# ELECTRON-.net
KiCad netlist of a schematic drawn in EAGLE
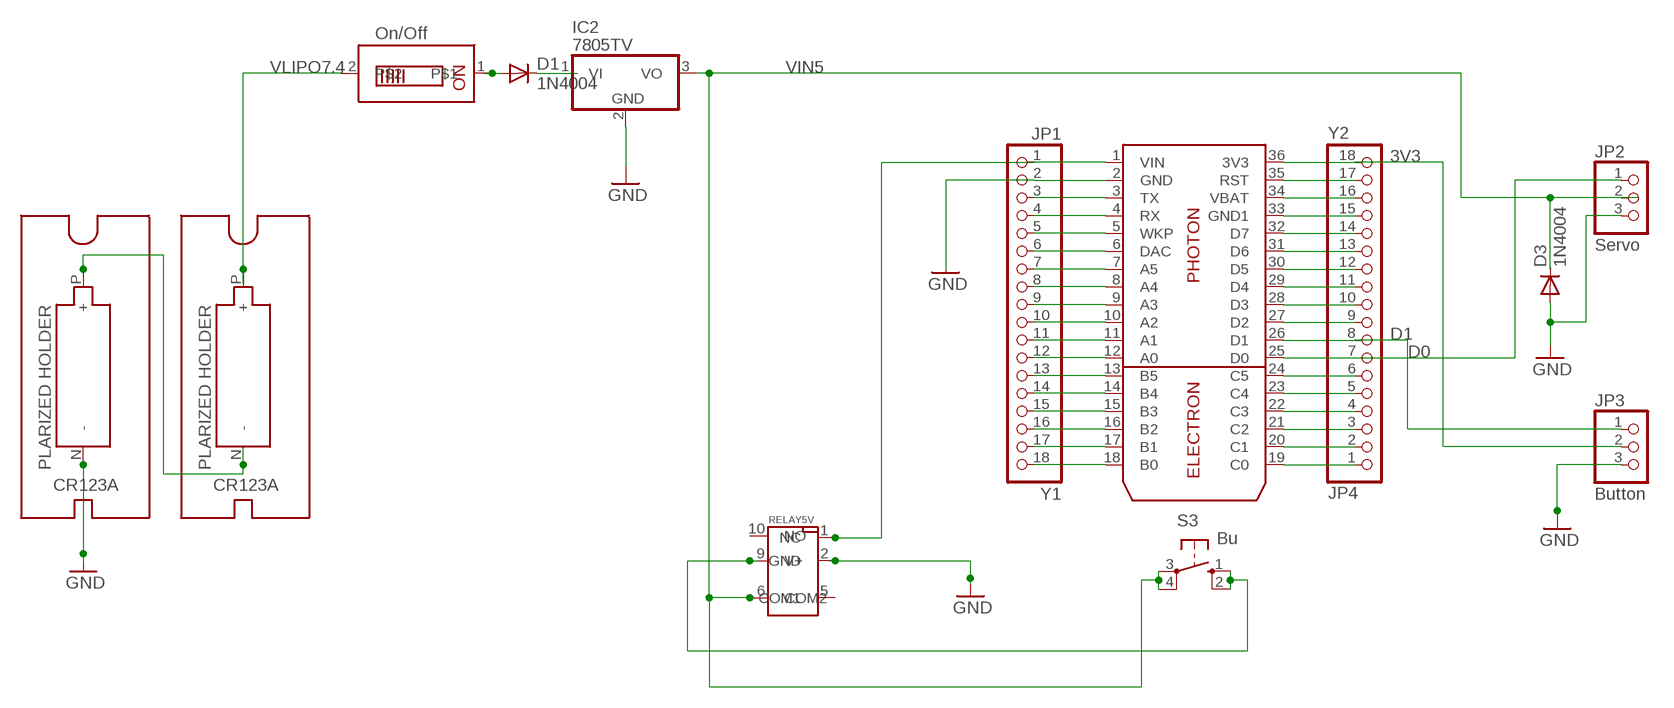
[diagram p0: schematic, sheet 1]

(export (version "E")
  (design (tool "Eeschema 10.0.6"))
  (components
    (comp (ref "D1")
      (value "1N4004")
      (footprint "eagle-import:DO41-10")
      (libsource (lib "eagle-import") (part "1N4004"))
    )
    (comp (ref "D3")
      (value "1N4004")
      (footprint "eagle-import:DO41-10")
      (libsource (lib "eagle-import") (part "1N4004"))
    )
    (comp (ref "ELECTRON2")
      (value "ELECTRON")
      (footprint "eagle-import:ELECTRON-U260")
      (libsource (lib "eagle-import") (part "ELECTRON"))
    )
    (comp (ref "IC2")
      (value "7805TV")
      (footprint "eagle-import:TO220V")
      (libsource (lib "eagle-import") (part "78TV05"))
    )
    (comp (ref "JP1")
      (value "Y1")
      (footprint "eagle-import:1X18")
      (libsource (lib "eagle-import") (part "PINHD-1X18"))
    )
    (comp (ref "JP2")
      (value "Servo")
      (footprint "eagle-import:1X03_90")
      (libsource (lib "eagle-import") (part "PINHD-1X3/90"))
    )
    (comp (ref "JP3")
      (value "Button")
      (footprint "eagle-import:1X03_90")
      (libsource (lib "eagle-import") (part "PINHD-1X3/90"))
    )
    (comp (ref "JP4")
      (value "Y2")
      (footprint "eagle-import:1X18")
      (libsource (lib "eagle-import") (part "PINHD-1X18"))
    )
    (comp (ref "S3")
      (value "Bu")
      (footprint "eagle-import:B3F-10XX")
      (fields (field (name "MPN") "B3F-1000"))
      (libsource (lib "eagle-import") (part "10-XX"))
    )
    (comp (ref "U$1")
      (value "POLARIZEDHOLDER-CR123A")
      (footprint "eagle-import:CRT123A")
      (libsource (lib "eagle-import") (part "POLARIZEDHOLDER-CR123A"))
    )
    (comp (ref "U$2")
      (value "POLARIZEDHOLDER-CR123A")
      (footprint "eagle-import:CRT123A")
      (libsource (lib "eagle-import") (part "POLARIZEDHOLDER-CR123A"))
    )
    (comp (ref "U$3")
      (value "SWIDGET")
      (footprint "eagle-import:GF-123-0054")
      (libsource (lib "eagle-import") (part "SWIDGET"))
    )
    (comp (ref "U$4")
      (value "RELAY5V")
      (footprint "eagle-import:RELAY5V-F")
      (libsource (lib "eagle-import") (part "RELAY5V"))
    )
  )
  (nets
    (net (code "1") (name "/3V3") (class "Default")
      (node (ref "ELECTRON2") (pin "36") (pinfunction "3V3_36") (pintype "bidirectional"))
      (node (ref "JP3") (pin "2") (pinfunction "2_2") (pintype "passive"))
      (node (ref "JP4") (pin "18") (pinfunction "18_18") (pintype "passive"))
    )
    (net (code "2") (name "/D0") (class "Default")
      (node (ref "ELECTRON2") (pin "25") (pinfunction "D0_25") (pintype "bidirectional"))
      (node (ref "JP2") (pin "1") (pinfunction "1_1") (pintype "passive"))
      (node (ref "JP4") (pin "7") (pinfunction "7_7") (pintype "passive"))
    )
    (net (code "3") (name "/D1") (class "Default")
      (node (ref "ELECTRON2") (pin "26") (pinfunction "D1_26") (pintype "bidirectional"))
      (node (ref "JP3") (pin "1") (pinfunction "1_1") (pintype "passive"))
      (node (ref "JP4") (pin "8") (pinfunction "8_8") (pintype "passive"))
    )
    (net (code "4") (name "/VIN5") (class "Default")
      (node (ref "D3") (pin "C") (pinfunction "C_C") (pintype "passive"))
      (node (ref "IC2") (pin "3") (pinfunction "VO_3") (pintype "passive"))
      (node (ref "JP2") (pin "2") (pinfunction "2_2") (pintype "passive"))
      (node (ref "S3") (pin "3") (pinfunction "P_3") (pintype "passive"))
      (node (ref "S3") (pin "4") (pinfunction "P1_4") (pintype "passive"))
      (node (ref "U$4") (pin "6") (pinfunction "COM2_6") (pintype "bidirectional"))
    )
    (net (code "5") (name "/VLIPO7.4") (class "Default")
      (node (ref "U$2") (pin "P") (pinfunction "+_P") (pintype "bidirectional"))
      (node (ref "U$3") (pin "2") (pinfunction "P$2_2") (pintype "bidirectional"))
    )
    (net (code "6") (name "GND") (class "Default")
      (node (ref "D3") (pin "A") (pinfunction "A_A") (pintype "passive"))
      (node (ref "ELECTRON2") (pin "2") (pinfunction "GND_2") (pintype "bidirectional"))
      (node (ref "IC2") (pin "2") (pinfunction "GND_2") (pintype "passive"))
      (node (ref "JP1") (pin "2") (pinfunction "2_2") (pintype "passive"))
      (node (ref "JP2") (pin "3") (pinfunction "3_3") (pintype "passive"))
      (node (ref "JP3") (pin "3") (pinfunction "3_3") (pintype "passive"))
      (node (ref "U$1") (pin "N") (pinfunction "-_N") (pintype "bidirectional"))
      (node (ref "U$4") (pin "2") (pinfunction "GND_2") (pintype "bidirectional"))
    )
    (net (code "7") (name "Net-(ELECTRON2-A0)") (class "Default")
      (node (ref "ELECTRON2") (pin "12") (pinfunction "A0_12") (pintype "bidirectional"))
      (node (ref "JP1") (pin "12") (pinfunction "12_12") (pintype "passive"))
    )
    (net (code "8") (name "Net-(ELECTRON2-A1)") (class "Default")
      (node (ref "ELECTRON2") (pin "11") (pinfunction "A1_11") (pintype "bidirectional"))
      (node (ref "JP1") (pin "11") (pinfunction "11_11") (pintype "passive"))
    )
    (net (code "9") (name "Net-(ELECTRON2-A2)") (class "Default")
      (node (ref "ELECTRON2") (pin "10") (pinfunction "A2_10") (pintype "bidirectional"))
      (node (ref "JP1") (pin "10") (pinfunction "10_10") (pintype "passive"))
    )
    (net (code "10") (name "Net-(ELECTRON2-A3)") (class "Default")
      (node (ref "ELECTRON2") (pin "9") (pinfunction "A3_9") (pintype "bidirectional"))
      (node (ref "JP1") (pin "9") (pinfunction "9_9") (pintype "passive"))
    )
    (net (code "11") (name "Net-(ELECTRON2-A4)") (class "Default")
      (node (ref "ELECTRON2") (pin "8") (pinfunction "A4_8") (pintype "bidirectional"))
      (node (ref "JP1") (pin "8") (pinfunction "8_8") (pintype "passive"))
    )
    (net (code "12") (name "Net-(ELECTRON2-A5)") (class "Default")
      (node (ref "ELECTRON2") (pin "7") (pinfunction "A5_7") (pintype "bidirectional"))
      (node (ref "JP1") (pin "7") (pinfunction "7_7") (pintype "passive"))
    )
    (net (code "13") (name "Net-(ELECTRON2-B0)") (class "Default")
      (node (ref "ELECTRON2") (pin "18") (pinfunction "B0_18") (pintype "bidirectional"))
      (node (ref "JP1") (pin "18") (pinfunction "18_18") (pintype "passive"))
    )
    (net (code "14") (name "Net-(ELECTRON2-B1)") (class "Default")
      (node (ref "ELECTRON2") (pin "17") (pinfunction "B1_17") (pintype "bidirectional"))
      (node (ref "JP1") (pin "17") (pinfunction "17_17") (pintype "passive"))
    )
    (net (code "15") (name "Net-(ELECTRON2-B2)") (class "Default")
      (node (ref "ELECTRON2") (pin "16") (pinfunction "B2_16") (pintype "bidirectional"))
      (node (ref "JP1") (pin "16") (pinfunction "16_16") (pintype "passive"))
    )
    (net (code "16") (name "Net-(ELECTRON2-B3)") (class "Default")
      (node (ref "ELECTRON2") (pin "15") (pinfunction "B3_15") (pintype "bidirectional"))
      (node (ref "JP1") (pin "15") (pinfunction "15_15") (pintype "passive"))
    )
    (net (code "17") (name "Net-(ELECTRON2-B4)") (class "Default")
      (node (ref "ELECTRON2") (pin "14") (pinfunction "B4_14") (pintype "bidirectional"))
      (node (ref "JP1") (pin "14") (pinfunction "14_14") (pintype "passive"))
    )
    (net (code "18") (name "Net-(ELECTRON2-B5)") (class "Default")
      (node (ref "ELECTRON2") (pin "13") (pinfunction "B5_13") (pintype "bidirectional"))
      (node (ref "JP1") (pin "13") (pinfunction "13_13") (pintype "passive"))
    )
    (net (code "19") (name "Net-(ELECTRON2-C0)") (class "Default")
      (node (ref "ELECTRON2") (pin "19") (pinfunction "C0_19") (pintype "bidirectional"))
      (node (ref "JP4") (pin "1") (pinfunction "1_1") (pintype "passive"))
    )
    (net (code "20") (name "Net-(ELECTRON2-C1)") (class "Default")
      (node (ref "ELECTRON2") (pin "20") (pinfunction "C1_20") (pintype "bidirectional"))
      (node (ref "JP4") (pin "2") (pinfunction "2_2") (pintype "passive"))
    )
    (net (code "21") (name "Net-(ELECTRON2-C2)") (class "Default")
      (node (ref "ELECTRON2") (pin "21") (pinfunction "C2_21") (pintype "bidirectional"))
      (node (ref "JP4") (pin "3") (pinfunction "3_3") (pintype "passive"))
    )
    (net (code "22") (name "Net-(ELECTRON2-C3)") (class "Default")
      (node (ref "ELECTRON2") (pin "22") (pinfunction "C3_22") (pintype "bidirectional"))
      (node (ref "JP4") (pin "4") (pinfunction "4_4") (pintype "passive"))
    )
    (net (code "23") (name "Net-(ELECTRON2-C4)") (class "Default")
      (node (ref "ELECTRON2") (pin "23") (pinfunction "C4_23") (pintype "bidirectional"))
      (node (ref "JP4") (pin "5") (pinfunction "5_5") (pintype "passive"))
    )
    (net (code "24") (name "Net-(ELECTRON2-C5)") (class "Default")
      (node (ref "ELECTRON2") (pin "24") (pinfunction "C5_24") (pintype "bidirectional"))
      (node (ref "JP4") (pin "6") (pinfunction "6_6") (pintype "passive"))
    )
    (net (code "25") (name "Net-(ELECTRON2-D2)") (class "Default")
      (node (ref "ELECTRON2") (pin "27") (pinfunction "D2_27") (pintype "bidirectional"))
      (node (ref "JP4") (pin "9") (pinfunction "9_9") (pintype "passive"))
    )
    (net (code "26") (name "Net-(ELECTRON2-D3)") (class "Default")
      (node (ref "ELECTRON2") (pin "28") (pinfunction "D3_28") (pintype "bidirectional"))
      (node (ref "JP4") (pin "10") (pinfunction "10_10") (pintype "passive"))
    )
    (net (code "27") (name "Net-(ELECTRON2-D4)") (class "Default")
      (node (ref "ELECTRON2") (pin "29") (pinfunction "D4_29") (pintype "bidirectional"))
      (node (ref "JP4") (pin "11") (pinfunction "11_11") (pintype "passive"))
    )
    (net (code "28") (name "Net-(ELECTRON2-D5)") (class "Default")
      (node (ref "ELECTRON2") (pin "30") (pinfunction "D5_30") (pintype "bidirectional"))
      (node (ref "JP4") (pin "12") (pinfunction "12_12") (pintype "passive"))
    )
    (net (code "29") (name "Net-(ELECTRON2-D6)") (class "Default")
      (node (ref "ELECTRON2") (pin "31") (pinfunction "D6_31") (pintype "bidirectional"))
      (node (ref "JP4") (pin "13") (pinfunction "13_13") (pintype "passive"))
    )
    (net (code "30") (name "Net-(ELECTRON2-D7)") (class "Default")
      (node (ref "ELECTRON2") (pin "32") (pinfunction "D7_32") (pintype "bidirectional"))
      (node (ref "JP4") (pin "14") (pinfunction "14_14") (pintype "passive"))
    )
    (net (code "31") (name "Net-(ELECTRON2-DAC)") (class "Default")
      (node (ref "ELECTRON2") (pin "6") (pinfunction "DAC_6") (pintype "bidirectional"))
      (node (ref "JP1") (pin "6") (pinfunction "6_6") (pintype "passive"))
    )
    (net (code "32") (name "Net-(ELECTRON2-GND1)") (class "Default")
      (node (ref "ELECTRON2") (pin "33") (pinfunction "GND1_33") (pintype "bidirectional"))
      (node (ref "JP4") (pin "15") (pinfunction "15_15") (pintype "passive"))
    )
    (net (code "33") (name "Net-(ELECTRON2-RST)") (class "Default")
      (node (ref "ELECTRON2") (pin "35") (pinfunction "RST_35") (pintype "bidirectional"))
      (node (ref "JP4") (pin "17") (pinfunction "17_17") (pintype "passive"))
    )
    (net (code "34") (name "Net-(ELECTRON2-RX)") (class "Default")
      (node (ref "ELECTRON2") (pin "4") (pinfunction "RX_4") (pintype "bidirectional"))
      (node (ref "JP1") (pin "4") (pinfunction "4_4") (pintype "passive"))
    )
    (net (code "35") (name "Net-(ELECTRON2-TX)") (class "Default")
      (node (ref "ELECTRON2") (pin "3") (pinfunction "TX_3") (pintype "bidirectional"))
      (node (ref "JP1") (pin "3") (pinfunction "3_3") (pintype "passive"))
    )
    (net (code "36") (name "Net-(ELECTRON2-VBAT)") (class "Default")
      (node (ref "ELECTRON2") (pin "34") (pinfunction "VBAT_34") (pintype "bidirectional"))
      (node (ref "JP4") (pin "16") (pinfunction "16_16") (pintype "passive"))
    )
    (net (code "37") (name "Net-(ELECTRON2-VIN)") (class "Default")
      (node (ref "ELECTRON2") (pin "1") (pinfunction "VIN_1") (pintype "bidirectional"))
      (node (ref "JP1") (pin "1") (pinfunction "1_1") (pintype "passive"))
      (node (ref "U$4") (pin "1") (pinfunction "NC_1") (pintype "bidirectional"))
    )
    (net (code "38") (name "Net-(ELECTRON2-WKP)") (class "Default")
      (node (ref "ELECTRON2") (pin "5") (pinfunction "WKP_5") (pintype "bidirectional"))
      (node (ref "JP1") (pin "5") (pinfunction "5_5") (pintype "passive"))
    )
    (net (code "39") (name "Net-(IC2-VI)") (class "Default")
      (node (ref "D1") (pin "C") (pinfunction "C_C") (pintype "passive"))
      (node (ref "IC2") (pin "1") (pinfunction "VI_1") (pintype "input"))
    )
    (net (code "40") (name "Net-(S3-S)") (class "Default")
      (node (ref "S3") (pin "1") (pinfunction "S_1") (pintype "passive"))
      (node (ref "S3") (pin "2") (pinfunction "S1_2") (pintype "passive"))
      (node (ref "U$4") (pin "9") (pinfunction "V+_9") (pintype "bidirectional"))
    )
    (net (code "41") (name "Net-(U$1-+)") (class "Default")
      (node (ref "U$1") (pin "P") (pinfunction "+_P") (pintype "bidirectional"))
      (node (ref "U$2") (pin "N") (pinfunction "-_N") (pintype "bidirectional"))
    )
    (net (code "42") (name "Net-(U$3-P$1)") (class "Default")
      (node (ref "D1") (pin "A") (pinfunction "A_A") (pintype "passive"))
      (node (ref "U$3") (pin "1") (pinfunction "P$1_1") (pintype "bidirectional"))
    )
    (net (code "43") (name "unconnected-(U$4-COM1-Pad5)") (class "Default")
      (node (ref "U$4") (pin "5") (pinfunction "COM1_5") (pintype "bidirectional"))
    )
    (net (code "44") (name "unconnected-(U$4-NO-Pad10)") (class "Default")
      (node (ref "U$4") (pin "10") (pinfunction "NO_10") (pintype "bidirectional"))
    )
  )
)
